# PlusBit_ExtraMemory.net
KiCad netlist of a schematic drawn in Altium Designer
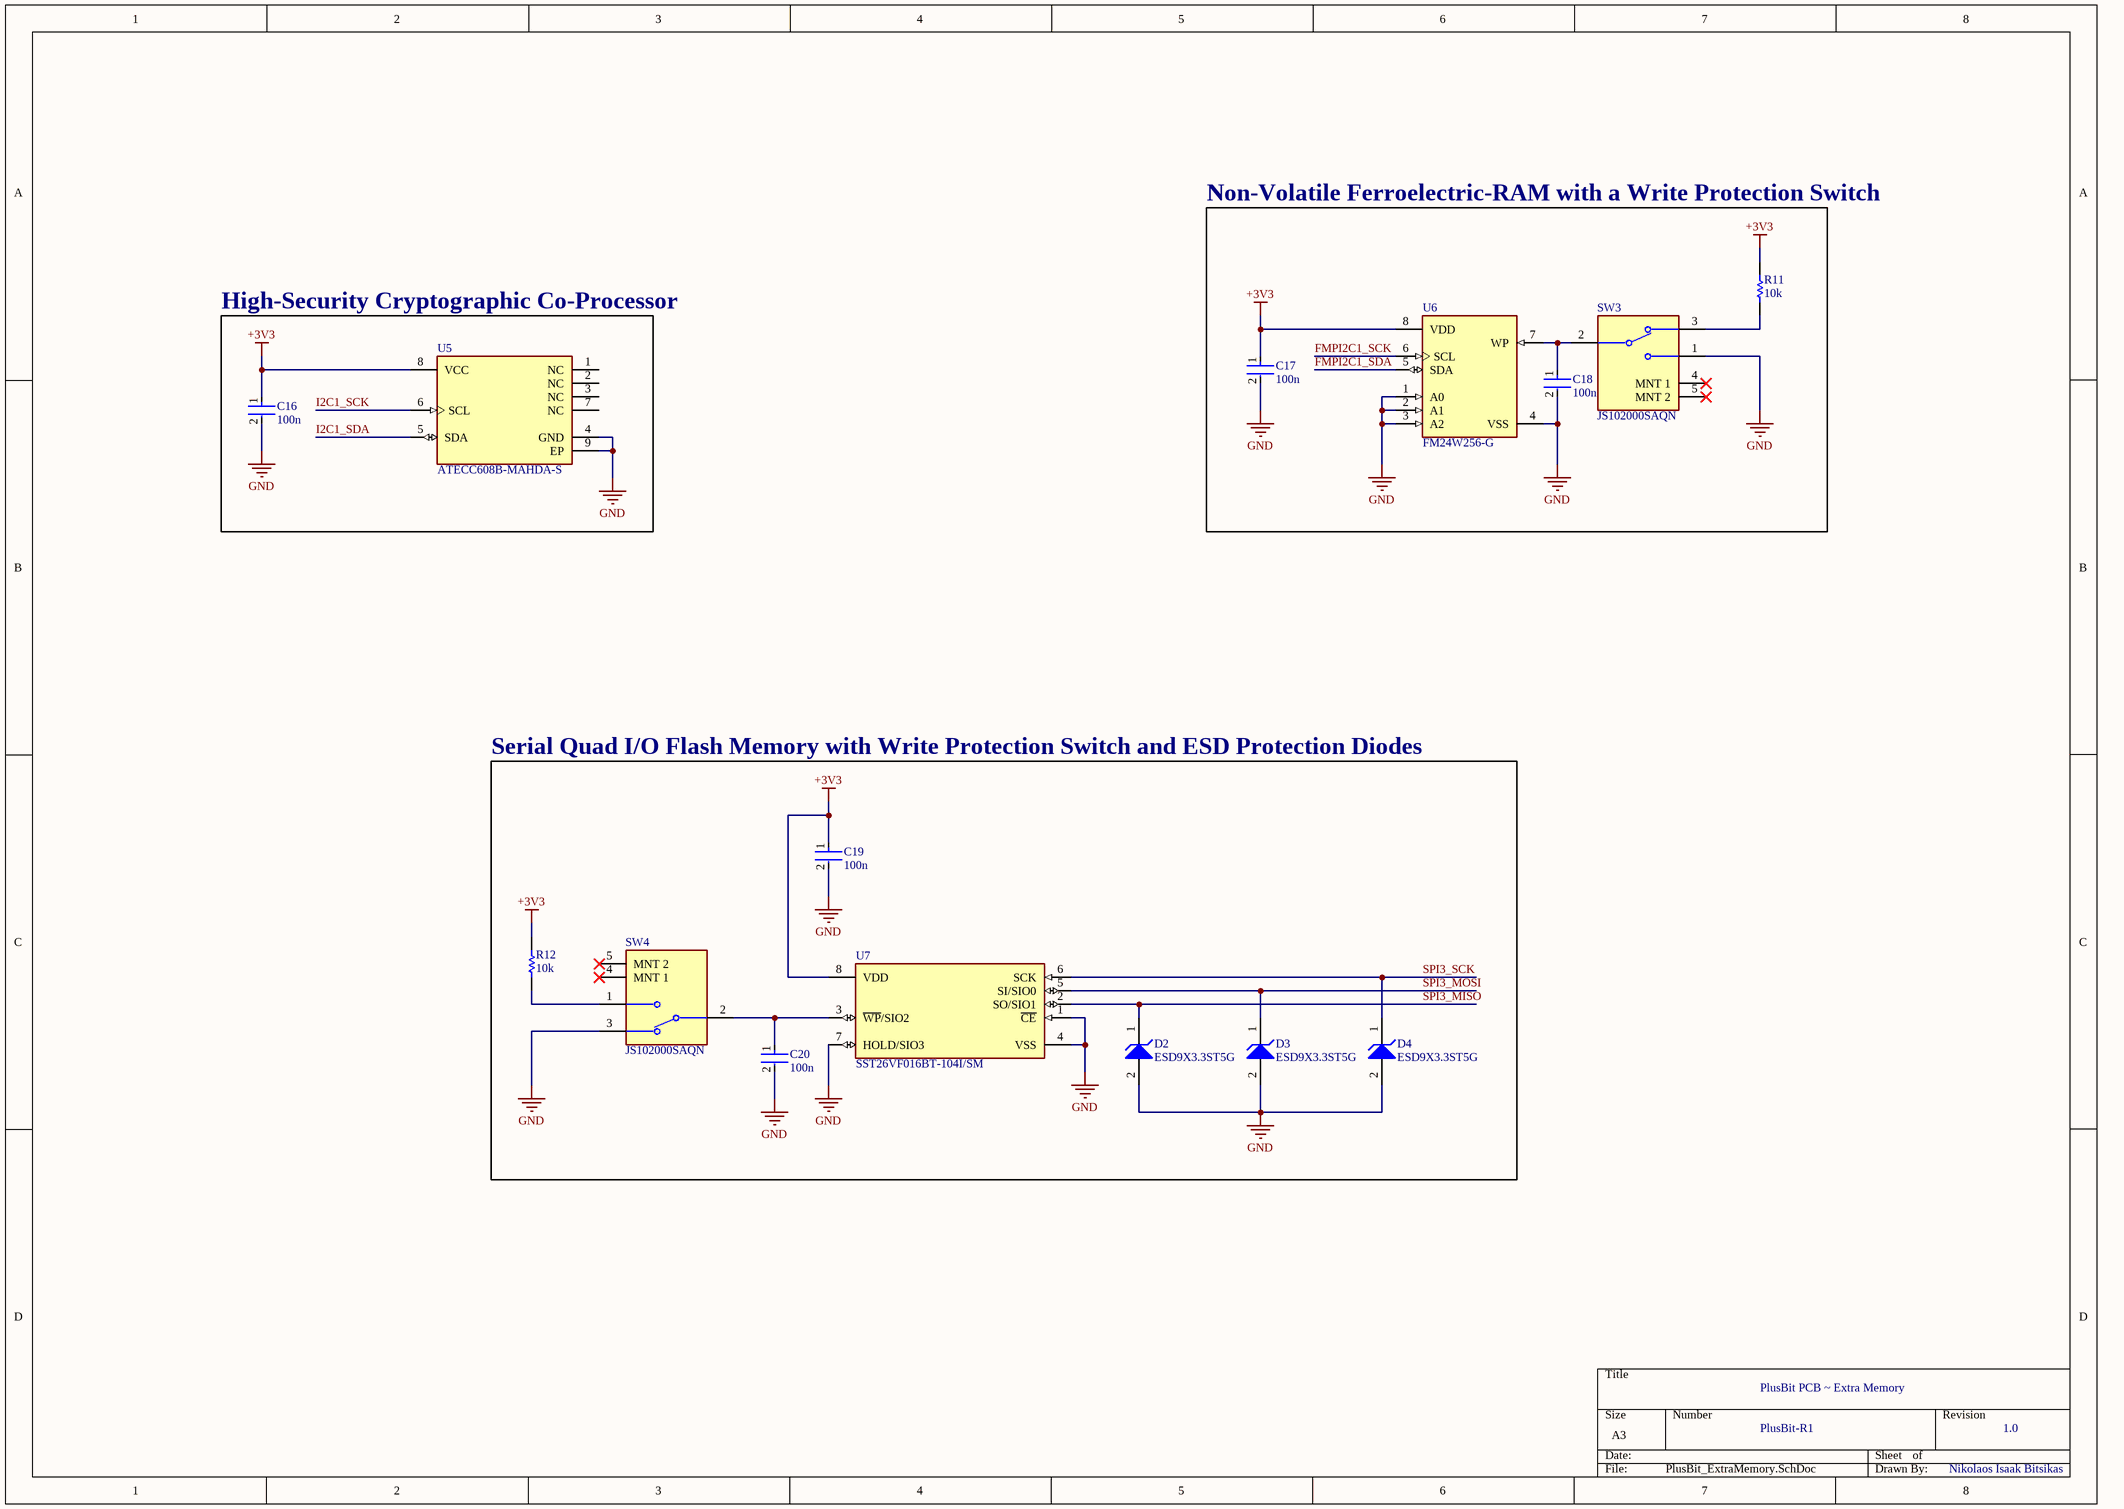
[diagram p0: PlusBit_ExtraMemory.SchDoc]

(export (version "E")
  (design (tool "Eeschema 10.0.6"))
  (components
    (comp (ref "C16")
      (value "100n")
      (footprint "FP-C0402-BB-MFG")
      (description "CAP CER 0.1UF 10V X5R 0402")
      (fields (field (name "MANUFACTURER") "Kemet") (field (name "TOLERANCE") "0.1"))
      (libsource (lib "Altium Content Vault") (part "b4654b650e69147ec39a6b967a45e02"))
    )
    (comp (ref "C17")
      (value "100n")
      (footprint "FP-C0402-BB-MFG")
      (description "CAP CER 0.1UF 10V X5R 0402")
      (fields (field (name "MANUFACTURER") "Kemet") (field (name "TOLERANCE") "0.1"))
      (libsource (lib "Altium Content Vault") (part "b4654b650e69147ec39a6b967a45e02"))
    )
    (comp (ref "C18")
      (value "100n")
      (footprint "FP-C0402-BB-MFG")
      (description "CAP CER 0.1UF 10V X5R 0402")
      (fields (field (name "MANUFACTURER") "Kemet") (field (name "TOLERANCE") "0.1"))
      (libsource (lib "Altium Content Vault") (part "b4654b650e69147ec39a6b967a45e02"))
    )
    (comp (ref "C19")
      (value "100n")
      (footprint "FP-C0402-BB-MFG")
      (description "CAP CER 0.1UF 10V X5R 0402")
      (fields (field (name "MANUFACTURER") "Kemet") (field (name "TOLERANCE") "0.1"))
      (libsource (lib "Altium Content Vault") (part "b4654b650e69147ec39a6b967a45e02"))
    )
    (comp (ref "C20")
      (value "100n")
      (footprint "FP-C0402-BB-MFG")
      (description "CAP CER 0.1UF 10V X5R 0402")
      (fields (field (name "MANUFACTURER") "Kemet") (field (name "TOLERANCE") "0.1"))
      (libsource (lib "Altium Content Vault") (part "b4654b650e69147ec39a6b967a45e02"))
    )
    (comp (ref "D2")
      (value "ESD9X3.3ST5G")
      (footprint "ONSC-SOD-923-2-514AA-01_V")
      (fields (field (name "MANUFACTURER") "On Semiconductor"))
      (libsource (lib "Altium Content Vault") (part "ONSC-K1A2-2"))
    )
    (comp (ref "D3")
      (value "ESD9X3.3ST5G")
      (footprint "ONSC-SOD-923-2-514AA-01_V")
      (fields (field (name "MANUFACTURER") "On Semiconductor"))
      (libsource (lib "Altium Content Vault") (part "ONSC-K1A2-2"))
    )
    (comp (ref "D4")
      (value "ESD9X3.3ST5G")
      (footprint "ONSC-SOD-923-2-514AA-01_V")
      (fields (field (name "MANUFACTURER") "On Semiconductor"))
      (libsource (lib "Altium Content Vault") (part "ONSC-K1A2-2"))
    )
    (comp (ref "R11")
      (value "10k")
      (footprint "RESC1608X55X25ML10T15")
      (description "Resistor, 10 KOhm, +/- 5%, 100 mW, -55 to 155 degC, 0603 (1608 Metric), RoHS, Tape and Reel")
      (fields (field (name "MANUFACTURER") "Yageo") (field (name "TOLERANCE") "5%"))
      (libsource (lib "Altium Content Vault") (part "RES-2"))
    )
    (comp (ref "R12")
      (value "10k")
      (footprint "RESC1608X55X25ML10T15")
      (description "Resistor, 10 KOhm, +/- 5%, 100 mW, -55 to 155 degC, 0603 (1608 Metric), RoHS, Tape and Reel")
      (fields (field (name "MANUFACTURER") "Yageo") (field (name "TOLERANCE") "5%"))
      (libsource (lib "Altium Content Vault") (part "RES-2"))
    )
    (comp (ref "SW3")
      (value "JS102000SAQN")
      (footprint "FP-JS102000SAQN-MFG")
      (description "SWITCH SLIDE SPDT 1MA 5V")
      (libsource (lib "") (part "6887e5fe807d9c5c2853bed39bc55bf_1"))
    )
    (comp (ref "SW4")
      (value "JS102000SAQN")
      (footprint "FP-JS102000SAQN-MFG")
      (description "SWITCH SLIDE SPDT 1MA 5V")
      (libsource (lib "Altium Content Vault") (part "6887e5fe807d9c5c2853bed39bc55bf"))
    )
    (comp (ref "U5")
      (value "ATECC608B-MAHDA-S")
      (footprint "FP-C04-21355-Q4B-IPC_B")
      (description "IC AUTHENTICATION CHIP")
      (libsource (lib "Altium Content Vault") (part "86edb8706b822f0bad86d9b788e16ff"))
    )
    (comp (ref "U6")
      (value "FM24W256-G")
      (footprint "FP-51-85066-MFG")
      (description "IC FRAM 256K I2C 1MHZ 8SOIC")
      (fields
        (field (name "OCTOPART") "https://octopart.com/fm24w256-g-cypress+semiconductor-25377035")
        (field (name "MANUFACTURER") "Cypress Semiconductor")
      )
      (libsource (lib "Altium Content Vault") (part "dc6e72fa4cedd9dd1402b36130de70d"))
    )
    (comp (ref "U7")
      (value "SST26VF016BT-104I/SM")
      (footprint "FP-C04-056-MFG")
      (description "SST26VF016BT-104I/SM Flash Memory, SQI Flash Memory, 16Mb 1.8V")
      (libsource (lib "Altium Content Vault") (part "d687d7f6dda7cf6c08011ccd1d740e3"))
    )
  )
  (nets
    (net (code "1") (name "+3V3") (class "Default")
      (node (ref "C16") (pin "1") (pinfunction "1_1") (pintype "passive"))
      (node (ref "C17") (pin "1") (pinfunction "1_1") (pintype "passive"))
      (node (ref "C19") (pin "1") (pinfunction "1_1") (pintype "passive"))
      (node (ref "R11") (pin "2") (pinfunction "2_2") (pintype "passive"))
      (node (ref "R12") (pin "2") (pinfunction "2_2") (pintype "passive"))
      (node (ref "U5") (pin "8") (pinfunction "VCC_8") (pintype "power_in"))
      (node (ref "U6") (pin "8") (pinfunction "VDD_8") (pintype "power_in"))
      (node (ref "U7") (pin "8") (pinfunction "VDD_8") (pintype "power_in"))
    )
    (net (code "2") (name "/FMPI2C1_SCK") (class "Default")
      (node (ref "U6") (pin "6") (pinfunction "SCL_6") (pintype "input"))
    )
    (net (code "3") (name "/FMPI2C1_SDA") (class "Default")
      (node (ref "U6") (pin "5") (pinfunction "SDA_5") (pintype "bidirectional"))
    )
    (net (code "4") (name "/I2C1_SCK") (class "Default")
      (node (ref "U5") (pin "6") (pinfunction "SCL_6") (pintype "input"))
    )
    (net (code "5") (name "/I2C1_SDA") (class "Default")
      (node (ref "U5") (pin "5") (pinfunction "SDA_5") (pintype "bidirectional"))
    )
    (net (code "6") (name "/SPI3_MISO") (class "Default")
      (node (ref "D2") (pin "1") (pinfunction "K_1") (pintype "passive"))
      (node (ref "U7") (pin "2") (pinfunction "SO/SIO1_2") (pintype "bidirectional"))
    )
    (net (code "7") (name "/SPI3_MOSI") (class "Default")
      (node (ref "D3") (pin "1") (pinfunction "K_1") (pintype "passive"))
      (node (ref "U7") (pin "5") (pinfunction "SI/SIO0_5") (pintype "bidirectional"))
    )
    (net (code "8") (name "/SPI3_SCK") (class "Default")
      (node (ref "D4") (pin "1") (pinfunction "K_1") (pintype "passive"))
      (node (ref "U7") (pin "6") (pinfunction "SCK_6") (pintype "input"))
    )
    (net (code "9") (name "GND") (class "Default")
      (node (ref "C16") (pin "2") (pinfunction "2_2") (pintype "passive"))
      (node (ref "C17") (pin "2") (pinfunction "2_2") (pintype "passive"))
      (node (ref "C18") (pin "2") (pinfunction "2_2") (pintype "passive"))
      (node (ref "C19") (pin "2") (pinfunction "2_2") (pintype "passive"))
      (node (ref "C20") (pin "2") (pinfunction "2_2") (pintype "passive"))
      (node (ref "D2") (pin "2") (pinfunction "A_2") (pintype "passive"))
      (node (ref "D3") (pin "2") (pinfunction "A_2") (pintype "passive"))
      (node (ref "D4") (pin "2") (pinfunction "A_2") (pintype "passive"))
      (node (ref "SW3") (pin "1") (pinfunction "1_1") (pintype "passive"))
      (node (ref "SW4") (pin "3") (pinfunction "3_3") (pintype "passive"))
      (node (ref "U5") (pin "4") (pinfunction "GND_4") (pintype "power_in"))
      (node (ref "U5") (pin "9") (pinfunction "EP_9") (pintype "passive"))
      (node (ref "U6") (pin "1") (pinfunction "A0_1") (pintype "input"))
      (node (ref "U6") (pin "2") (pinfunction "A1_2") (pintype "input"))
      (node (ref "U6") (pin "3") (pinfunction "A2_3") (pintype "input"))
      (node (ref "U6") (pin "4") (pinfunction "VSS_4") (pintype "power_in"))
      (node (ref "U7") (pin "1") (pinfunction "~{CE}_1") (pintype "input"))
      (node (ref "U7") (pin "4") (pinfunction "VSS_4") (pintype "power_in"))
      (node (ref "U7") (pin "7") (pinfunction "HOLD/SIO3_7") (pintype "bidirectional"))
    )
    (net (code "10") (name "Net-(R11-Pad1)") (class "Default")
      (node (ref "R11") (pin "1") (pinfunction "1_1") (pintype "passive"))
      (node (ref "SW3") (pin "3") (pinfunction "3_3") (pintype "passive"))
    )
    (net (code "11") (name "Net-(R12-Pad1)") (class "Default")
      (node (ref "R12") (pin "1") (pinfunction "1_1") (pintype "passive"))
      (node (ref "SW4") (pin "1") (pinfunction "1_1") (pintype "passive"))
    )
    (net (code "12") (name "Net-(SW3-C)") (class "Default")
      (node (ref "C18") (pin "1") (pinfunction "1_1") (pintype "passive"))
      (node (ref "SW3") (pin "2") (pinfunction "C_2") (pintype "passive"))
      (node (ref "U6") (pin "7") (pinfunction "WP_7") (pintype "input"))
    )
    (net (code "13") (name "Net-(SW4-C)") (class "Default")
      (node (ref "C20") (pin "1") (pinfunction "1_1") (pintype "passive"))
      (node (ref "SW4") (pin "2") (pinfunction "C_2") (pintype "passive"))
      (node (ref "U7") (pin "3") (pinfunction "~{WP}/SIO2_3") (pintype "bidirectional"))
    )
    (net (code "14") (name "unconnected-(SW3-MNT_1-Pad4)") (class "Default")
      (node (ref "SW3") (pin "4") (pinfunction "MNT_1_4") (pintype "passive+no_connect"))
    )
    (net (code "15") (name "unconnected-(SW3-MNT_2-Pad5)") (class "Default")
      (node (ref "SW3") (pin "5") (pinfunction "MNT_2_5") (pintype "passive+no_connect"))
    )
    (net (code "16") (name "unconnected-(SW4-MNT_1-Pad4)") (class "Default")
      (node (ref "SW4") (pin "4") (pinfunction "MNT_1_4") (pintype "passive+no_connect"))
    )
    (net (code "17") (name "unconnected-(SW4-MNT_2-Pad5)") (class "Default")
      (node (ref "SW4") (pin "5") (pinfunction "MNT_2_5") (pintype "passive+no_connect"))
    )
    (net (code "18") (name "unconnected-(U5-NC-Pad1)") (class "Default")
      (node (ref "U5") (pin "1") (pinfunction "NC_1") (pintype "passive"))
    )
    (net (code "19") (name "unconnected-(U5-NC-Pad2)") (class "Default")
      (node (ref "U5") (pin "2") (pinfunction "NC_2") (pintype "passive"))
    )
    (net (code "20") (name "unconnected-(U5-NC-Pad3)") (class "Default")
      (node (ref "U5") (pin "3") (pinfunction "NC_3") (pintype "passive"))
    )
    (net (code "21") (name "unconnected-(U5-NC-Pad7)") (class "Default")
      (node (ref "U5") (pin "7") (pinfunction "NC_7") (pintype "passive"))
    )
  )
)
